# Multiple_Power_Supply_schematic.net
KiCad netlist of a schematic drawn in Altium Designer
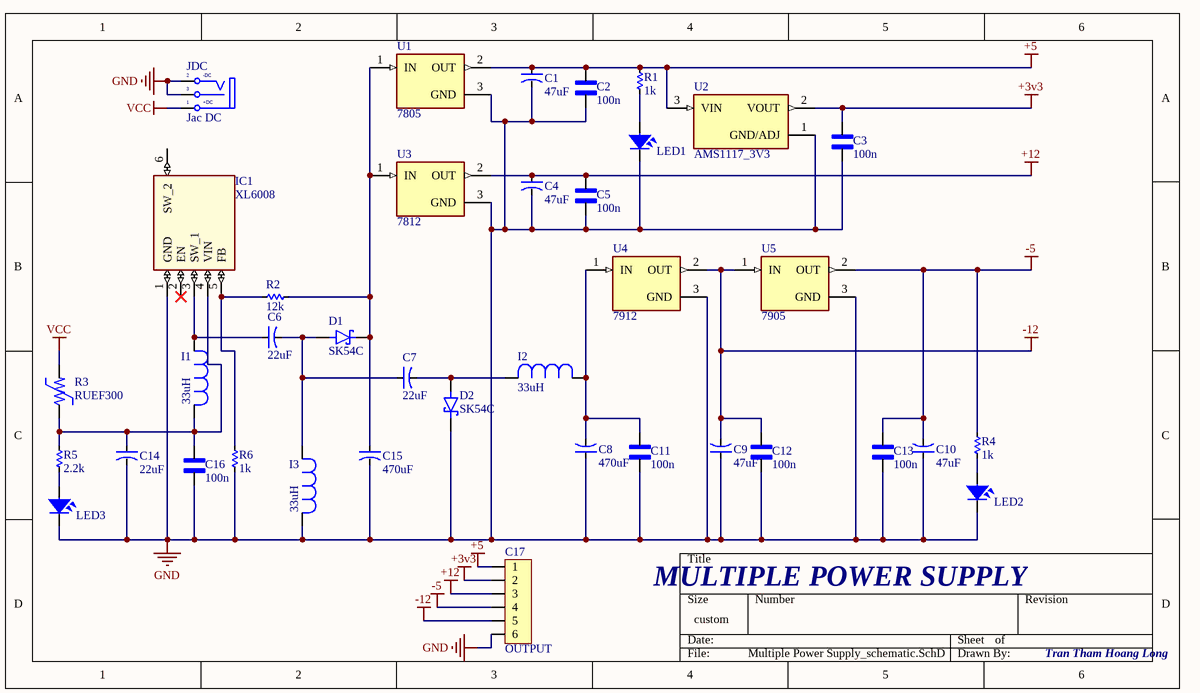
[diagram p0: Multiple Power Supply_schematic.SchDoc]

(export (version "E")
  (design (tool "Eeschema 10.0.6"))
  (components
    (comp (ref "C1")
      (value "47uF")
      (footprint "CAP-ALU-SMD-D")
      (description "Polarized Capacitor (Axial)")
      (fields (field (name "PUBLISHER") "Altium Limited"))
      (libsource (lib "LIBRARY") (part "CN-ALU-SMD"))
    )
    (comp (ref "C2")
      (value "100n")
      (footprint "Cap 100nF 50V 1206")
      (description "Cap Ceramic")
      (libsource (lib "HoangLong_Library") (part "Cap SMD"))
    )
    (comp (ref "C3")
      (value "100n")
      (footprint "Cap 100nF 50V 1206")
      (description "Cap Ceramic")
      (libsource (lib "HoangLong_Library") (part "Cap SMD"))
    )
    (comp (ref "C4")
      (value "47uF")
      (footprint "CAP-ALU-SMD-D")
      (description "Polarized Capacitor (Axial)")
      (fields (field (name "PUBLISHER") "Altium Limited"))
      (libsource (lib "LIBRARY") (part "CN-ALU-SMD"))
    )
    (comp (ref "C5")
      (value "100n")
      (footprint "Cap 100nF 50V 1206")
      (description "Cap Ceramic")
      (libsource (lib "HoangLong_Library") (part "Cap SMD"))
    )
    (comp (ref "C6")
      (value "22uF")
      (footprint "CAP-ALU-SMD-D")
      (description "Polarized Capacitor (Axial)")
      (fields (field (name "PUBLISHER") "Altium Limited"))
      (libsource (lib "LIBRARY") (part "CN-ALU-SMD"))
    )
    (comp (ref "C7")
      (value "22uF")
      (footprint "CAP-ALU-SMD-D")
      (description "Polarized Capacitor (Axial)")
      (fields (field (name "PUBLISHER") "Altium Limited"))
      (libsource (lib "LIBRARY") (part "CN-ALU-SMD"))
    )
    (comp (ref "C8")
      (value "470uF")
      (footprint "CAP-ALU-SMD-5x5.5x1.4")
      (description "Polarized Capacitor (Axial)")
      (fields (field (name "PUBLISHER") "Altium Limited"))
      (libsource (lib "LIBRARY") (part "CN-ALU-SMD"))
    )
    (comp (ref "C9")
      (value "47uF")
      (footprint "CAP-ALU-SMD-D")
      (description "Polarized Capacitor (Axial)")
      (fields (field (name "PUBLISHER") "Altium Limited"))
      (libsource (lib "LIBRARY") (part "CN-ALU-SMD"))
    )
    (comp (ref "C10")
      (value "47uF")
      (footprint "CAP-ALU-SMD-D")
      (description "Polarized Capacitor (Axial)")
      (fields (field (name "PUBLISHER") "Altium Limited"))
      (libsource (lib "LIBRARY") (part "CN-ALU-SMD"))
    )
    (comp (ref "C11")
      (value "100n")
      (footprint "Cap 100nF 50V 1206")
      (description "Cap Ceramic")
      (libsource (lib "HoangLong_Library") (part "Cap SMD"))
    )
    (comp (ref "C12")
      (value "100n")
      (footprint "Cap 100nF 50V 1206")
      (description "Cap Ceramic")
      (libsource (lib "HoangLong_Library") (part "Cap SMD"))
    )
    (comp (ref "C13")
      (value "100n")
      (footprint "Cap 100nF 50V 1206")
      (description "Cap Ceramic")
      (libsource (lib "HoangLong_Library") (part "Cap SMD"))
    )
    (comp (ref "C14")
      (value "22uF")
      (footprint "CAP-ALU-SMD-D")
      (description "Polarized Capacitor (Axial)")
      (fields (field (name "PUBLISHER") "Altium Limited"))
      (libsource (lib "LIBRARY") (part "CN-ALU-SMD"))
    )
    (comp (ref "C15")
      (value "470uF")
      (footprint "CAP-ALU-SMD-5x5.5x1.4")
      (description "Polarized Capacitor (Axial)")
      (fields (field (name "PUBLISHER") "Altium Limited"))
      (libsource (lib "LIBRARY") (part "CN-ALU-SMD"))
    )
    (comp (ref "C16")
      (value "100n")
      (footprint "Cap 100nF 50V 1206")
      (description "Cap Ceramic")
      (libsource (lib "HoangLong_Library") (part "Cap SMD"))
    )
    (comp (ref "C17")
      (value "OUTPUT")
      (footprint "Header6")
      (description "Header IDC, 6 x 1 Pin Vertical 2.54mm Pitch (Non-Boxed, Male)")
      (fields
        (field (name "MANUFACTURER") "Würth Elektronik eiSos GmbH")
        (field (name "PARTNO") "613002143121")
        (field (name "CREATED BY") "Karrer Zheng")
      )
      (libsource (lib "LIBRARY") (part "Header6"))
    )
    (comp (ref "D1")
      (value "SK54C")
      (footprint "SK54C")
      (description "Diode 5A 40V")
      (libsource (lib "HoangLong_Library") (part "SK54C"))
    )
    (comp (ref "D2")
      (value "SK54C")
      (footprint "SK54C")
      (description "Diode 5A 40V")
      (libsource (lib "HoangLong_Library") (part "SK54C"))
    )
    (comp (ref "I1")
      (value "33uH")
      (footprint "Inductor-CDRH127")
      (description "CDRH127")
      (libsource (lib "HoangLong_Library") (part "Inductor_SMD"))
    )
    (comp (ref "I2")
      (value "33uH")
      (footprint "Inductor-CDRH127")
      (description "CDRH127")
      (libsource (lib "HoangLong_Library") (part "Inductor_SMD"))
    )
    (comp (ref "I3")
      (value "33uH")
      (footprint "Inductor-CDRH127")
      (description "CDRH127")
      (libsource (lib "HoangLong_Library") (part "Inductor_SMD"))
    )
    (comp (ref "IC1")
      (value "XL6008")
      (footprint "XL6008")
      (libsource (lib "HoangLong_Library") (part "XL6008"))
    )
    (comp (ref "JDC")
      (value "Jac DC")
      (footprint "DC0")
      (description "Jac DC input")
      (libsource (lib "LIBRARY") (part "DCIN"))
    )
    (comp (ref "LED1") (value "LED") (footprint "LED-0805-Red") (libsource (lib "LIBRARY") (part "LED SMD")))
    (comp (ref "LED2") (value "LED") (footprint "LED-0805-Red") (libsource (lib "LIBRARY") (part "LED SMD")))
    (comp (ref "LED3") (value "LED") (footprint "LED-0805-Red") (libsource (lib "LIBRARY") (part "LED SMD")))
    (comp (ref "R1")
      (value "1k")
      (footprint "RES-SMD-0805")
      (description "Resistor")
      (fields
        (field (name "MANUFACTURER") "Generic Components")
        (field (name "PUBLISHER") "Altium Hobart Technology Centre")
      )
      (libsource (lib "LIBRARY") (part "Res-SMD"))
    )
    (comp (ref "R2")
      (value "12k")
      (footprint "RES-SMD-0805")
      (description "Resistor")
      (fields
        (field (name "MANUFACTURER") "Generic Components")
        (field (name "PUBLISHER") "Altium Hobart Technology Centre")
      )
      (libsource (lib "LIBRARY") (part "Res-SMD"))
    )
    (comp (ref "R3")
      (value "RUEF300")
      (footprint "RUEF300")
      (description "Polymeric PTC Resettable Fuse 30V 3 A Ih Through Hole Radial, Disc")
      (libsource (lib "HoangLong_Library") (part "RUEF300"))
    )
    (comp (ref "R4")
      (value "1k")
      (footprint "RES-SMD-0805")
      (description "Resistor")
      (fields
        (field (name "MANUFACTURER") "Generic Components")
        (field (name "PUBLISHER") "Altium Hobart Technology Centre")
      )
      (libsource (lib "LIBRARY") (part "Res-SMD"))
    )
    (comp (ref "R5")
      (value "2.2k")
      (footprint "RES-SMD-0805")
      (description "Resistor")
      (fields
        (field (name "MANUFACTURER") "Generic Components")
        (field (name "PUBLISHER") "Altium Hobart Technology Centre")
      )
      (libsource (lib "LIBRARY") (part "Res-SMD"))
    )
    (comp (ref "R6")
      (value "1k")
      (footprint "RES-SMD-0805")
      (description "Resistor")
      (fields
        (field (name "MANUFACTURER") "Generic Components")
        (field (name "PUBLISHER") "Altium Hobart Technology Centre")
      )
      (libsource (lib "LIBRARY") (part "Res-SMD"))
    )
    (comp (ref "U1")
      (value "7805")
      (footprint "TO-263")
      (description "Linear Voltage Regulator IC Positive Fixed 1 Output 1.5A D2PAK")
      (libsource (lib "HoangLong_Library") (part "LM78xx"))
    )
    (comp (ref "U2")
      (value "AMS1117_3V3")
      (footprint "AMS1117_3v3")
      (libsource (lib "HoangLong_Library") (part "AMS1117_3V3"))
    )
    (comp (ref "U3")
      (value "7812")
      (footprint "TO-263")
      (description "Linear Voltage Regulator IC Positive Fixed 1 Output 1.5A D2PAK")
      (libsource (lib "HoangLong_Library") (part "LM78xx"))
    )
    (comp (ref "U4")
      (value "7912")
      (footprint "TO-263")
      (description "Linear Voltage Regulator IC Positive Fixed 1 Output 1.5A D2PAK")
      (libsource (lib "HoangLong_Library") (part "LM78xx"))
    )
    (comp (ref "U5")
      (value "7905")
      (footprint "TO-263")
      (description "Linear Voltage Regulator IC Positive Fixed 1 Output 1.5A D2PAK")
      (libsource (lib "HoangLong_Library") (part "LM78xx"))
    )
  )
  (nets
    (net (code "1") (name "+3v3") (class "Default")
      (node (ref "C17") (pin "2") (pinfunction "2_2") (pintype "passive"))
      (node (ref "C3") (pin "2") (pinfunction "2_2") (pintype "passive"))
      (node (ref "U2") (pin "2") (pinfunction "VOUT_2") (pintype "output"))
    )
    (net (code "2") (name "+5") (class "Default")
      (node (ref "C1") (pin "1") (pinfunction "1_1") (pintype "passive"))
      (node (ref "C17") (pin "1") (pinfunction "1_1") (pintype "passive"))
      (node (ref "C2") (pin "2") (pinfunction "2_2") (pintype "passive"))
      (node (ref "R1") (pin "1") (pinfunction "1_1") (pintype "passive"))
      (node (ref "U1") (pin "2") (pinfunction "OUT_2") (pintype "output"))
      (node (ref "U2") (pin "3") (pinfunction "VIN_3") (pintype "input"))
    )
    (net (code "3") (name "+12") (class "Default")
      (node (ref "C17") (pin "3") (pinfunction "3_3") (pintype "passive"))
      (node (ref "C4") (pin "1") (pinfunction "1_1") (pintype "passive"))
      (node (ref "C5") (pin "2") (pinfunction "2_2") (pintype "passive"))
      (node (ref "U3") (pin "2") (pinfunction "OUT_2") (pintype "output"))
    )
    (net (code "4") (name "-5") (class "Default")
      (node (ref "C10") (pin "2") (pinfunction "2_2") (pintype "passive"))
      (node (ref "C13") (pin "2") (pinfunction "2_2") (pintype "passive"))
      (node (ref "C17") (pin "4") (pinfunction "4_4") (pintype "passive"))
      (node (ref "R4") (pin "1") (pinfunction "1_1") (pintype "passive"))
      (node (ref "U5") (pin "2") (pinfunction "OUT_2") (pintype "output"))
    )
    (net (code "5") (name "-12") (class "Default")
      (node (ref "C12") (pin "2") (pinfunction "2_2") (pintype "passive"))
      (node (ref "C17") (pin "5") (pinfunction "5_5") (pintype "passive"))
      (node (ref "C9") (pin "2") (pinfunction "2_2") (pintype "passive"))
      (node (ref "U4") (pin "2") (pinfunction "OUT_2") (pintype "output"))
      (node (ref "U5") (pin "1") (pinfunction "IN_1") (pintype "input"))
    )
    (net (code "6") (name "GND") (class "Default")
      (node (ref "C1") (pin "2") (pinfunction "2_2") (pintype "passive"))
      (node (ref "C10") (pin "1") (pinfunction "1_1") (pintype "passive"))
      (node (ref "C11") (pin "1") (pinfunction "1_1") (pintype "passive"))
      (node (ref "C12") (pin "1") (pinfunction "1_1") (pintype "passive"))
      (node (ref "C13") (pin "1") (pinfunction "1_1") (pintype "passive"))
      (node (ref "C14") (pin "2") (pinfunction "2_2") (pintype "passive"))
      (node (ref "C15") (pin "2") (pinfunction "2_2") (pintype "passive"))
      (node (ref "C16") (pin "1") (pinfunction "1_1") (pintype "passive"))
      (node (ref "C17") (pin "6") (pinfunction "6_6") (pintype "passive"))
      (node (ref "C2") (pin "1") (pinfunction "1_1") (pintype "passive"))
      (node (ref "C3") (pin "1") (pinfunction "1_1") (pintype "passive"))
      (node (ref "C4") (pin "2") (pinfunction "2_2") (pintype "passive"))
      (node (ref "C5") (pin "1") (pinfunction "1_1") (pintype "passive"))
      (node (ref "C8") (pin "1") (pinfunction "1_1") (pintype "passive"))
      (node (ref "C9") (pin "1") (pinfunction "1_1") (pintype "passive"))
      (node (ref "D2") (pin "C") (pinfunction "K_C") (pintype "passive"))
      (node (ref "I3") (pin "1") (pinfunction "1_1") (pintype "passive"))
      (node (ref "IC1") (pin "1") (pinfunction "GND_1") (pintype "bidirectional"))
      (node (ref "JDC") (pin "2") (pinfunction "TN_2") (pintype "passive"))
      (node (ref "JDC") (pin "3") (pinfunction "S_3") (pintype "power_in"))
      (node (ref "LED1") (pin "2") (pinfunction "2_2") (pintype "passive"))
      (node (ref "LED2") (pin "2") (pinfunction "2_2") (pintype "passive"))
      (node (ref "LED3") (pin "2") (pinfunction "2_2") (pintype "passive"))
      (node (ref "R6") (pin "2") (pinfunction "2_2") (pintype "passive"))
      (node (ref "U1") (pin "3") (pinfunction "GND_3") (pintype "power_in"))
      (node (ref "U2") (pin "1") (pinfunction "GND/ADJ_1") (pintype "power_in"))
      (node (ref "U3") (pin "3") (pinfunction "GND_3") (pintype "power_in"))
      (node (ref "U4") (pin "3") (pinfunction "GND_3") (pintype "power_in"))
      (node (ref "U5") (pin "3") (pinfunction "GND_3") (pintype "power_in"))
    )
    (net (code "7") (name "Net-(C6-Pad2)") (class "Default")
      (node (ref "C6") (pin "2") (pinfunction "2_2") (pintype "passive"))
      (node (ref "C7") (pin "1") (pinfunction "1_1") (pintype "passive"))
      (node (ref "D1") (pin "A") (pinfunction "A_A") (pintype "passive"))
      (node (ref "I3") (pin "2") (pinfunction "2_2") (pintype "passive"))
    )
    (net (code "8") (name "Net-(C7-Pad2)") (class "Default")
      (node (ref "C7") (pin "2") (pinfunction "2_2") (pintype "passive"))
      (node (ref "D2") (pin "A") (pinfunction "A_A") (pintype "passive"))
      (node (ref "I2") (pin "2") (pinfunction "2_2") (pintype "passive"))
    )
    (net (code "9") (name "Net-(D1-K)") (class "Default")
      (node (ref "C15") (pin "1") (pinfunction "1_1") (pintype "passive"))
      (node (ref "D1") (pin "C") (pinfunction "K_C") (pintype "passive"))
      (node (ref "R2") (pin "2") (pinfunction "2_2") (pintype "passive"))
      (node (ref "U1") (pin "1") (pinfunction "IN_1") (pintype "input"))
      (node (ref "U3") (pin "1") (pinfunction "IN_1") (pintype "input"))
    )
    (net (code "10") (name "Net-(IC1-FB)") (class "Default")
      (node (ref "IC1") (pin "5") (pinfunction "FB_5") (pintype "bidirectional"))
      (node (ref "R2") (pin "1") (pinfunction "1_1") (pintype "passive"))
      (node (ref "R6") (pin "1") (pinfunction "1_1") (pintype "passive"))
    )
    (net (code "11") (name "Net-(IC1-SW_1)") (class "Default")
      (node (ref "C6") (pin "1") (pinfunction "1_1") (pintype "passive"))
      (node (ref "I1") (pin "2") (pinfunction "2_2") (pintype "passive"))
      (node (ref "IC1") (pin "3") (pinfunction "SW_1_3") (pintype "bidirectional"))
    )
    (net (code "12") (name "Net-(IC1-VIN)") (class "Default")
      (node (ref "C14") (pin "1") (pinfunction "1_1") (pintype "passive"))
      (node (ref "C16") (pin "2") (pinfunction "2_2") (pintype "passive"))
      (node (ref "I1") (pin "1") (pinfunction "1_1") (pintype "passive"))
      (node (ref "IC1") (pin "4") (pinfunction "VIN_4") (pintype "bidirectional"))
      (node (ref "R3") (pin "P$1") (pinfunction "1_P$1") (pintype "passive"))
      (node (ref "R5") (pin "1") (pinfunction "1_1") (pintype "passive"))
    )
    (net (code "13") (name "Net-(LED1-Pad1)") (class "Default")
      (node (ref "LED1") (pin "1") (pinfunction "1_1") (pintype "passive"))
      (node (ref "R1") (pin "2") (pinfunction "2_2") (pintype "passive"))
    )
    (net (code "14") (name "Net-(LED2-Pad1)") (class "Default")
      (node (ref "LED2") (pin "1") (pinfunction "1_1") (pintype "passive"))
      (node (ref "R4") (pin "2") (pinfunction "2_2") (pintype "passive"))
    )
    (net (code "15") (name "Net-(LED3-Pad1)") (class "Default")
      (node (ref "LED3") (pin "1") (pinfunction "1_1") (pintype "passive"))
      (node (ref "R5") (pin "2") (pinfunction "2_2") (pintype "passive"))
    )
    (net (code "16") (name "Net-(U4-IN)") (class "Default")
      (node (ref "C11") (pin "2") (pinfunction "2_2") (pintype "passive"))
      (node (ref "C8") (pin "2") (pinfunction "2_2") (pintype "passive"))
      (node (ref "I2") (pin "1") (pinfunction "1_1") (pintype "passive"))
      (node (ref "U4") (pin "1") (pinfunction "IN_1") (pintype "input"))
    )
    (net (code "17") (name "VCC") (class "Default")
      (node (ref "JDC") (pin "1") (pinfunction "T_1") (pintype "passive"))
      (node (ref "R3") (pin "P$2") (pinfunction "2_P$2") (pintype "passive"))
    )
    (net (code "18") (name "unconnected-(IC1-EN-Pad2)") (class "Default")
      (node (ref "IC1") (pin "2") (pinfunction "EN_2") (pintype "bidirectional+no_connect"))
    )
    (net (code "19") (name "unconnected-(IC1-SW_2-Pad6)") (class "Default")
      (node (ref "IC1") (pin "6") (pinfunction "SW_2_6") (pintype "bidirectional"))
    )
  )
)
